# chainable_shift_register.net
KiCad netlist of a schematic drawn in EAGLE
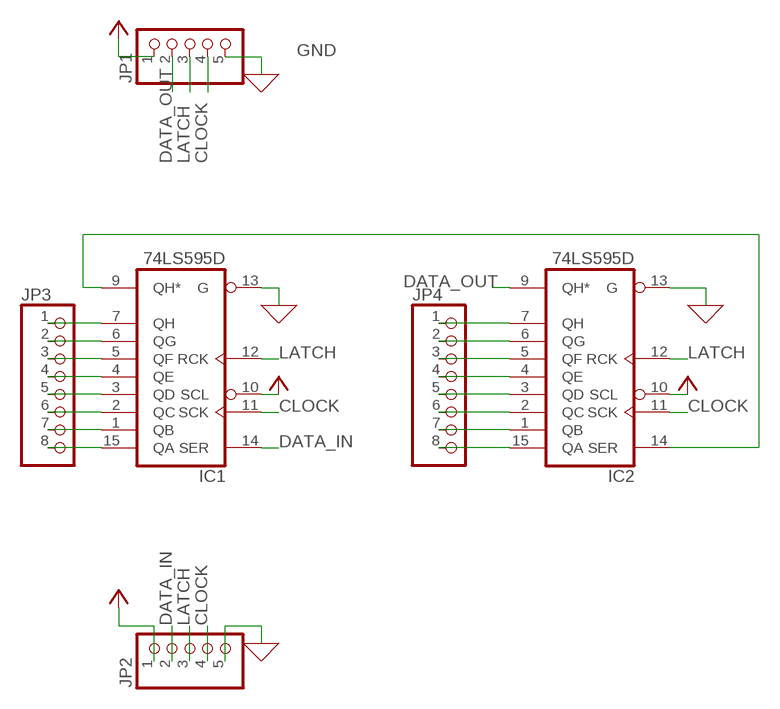
[diagram p0: schematic, sheet 1]

(export (version "E")
  (design (tool "Eeschema 10.0.6"))
  (components
    (comp (ref "IC1")
      (value "74LS595D")
      (footprint "eagle-import:SO16")
      (libsource (lib "eagle-import") (part "74595DLS"))
    )
    (comp (ref "IC2")
      (value "74LS595D")
      (footprint "eagle-import:SO16")
      (libsource (lib "eagle-import") (part "74595DLS"))
    )
    (comp (ref "JP1")
      (value "PINHD-1X5")
      (footprint "eagle-import:1X05")
      (libsource (lib "eagle-import") (part "PINHD-1X5"))
    )
    (comp (ref "JP2")
      (value "PINHD-1X5")
      (footprint "eagle-import:1X05")
      (libsource (lib "eagle-import") (part "PINHD-1X5"))
    )
    (comp (ref "JP3")
      (value "PINHD-1X8")
      (footprint "eagle-import:1X08")
      (libsource (lib "eagle-import") (part "PINHD-1X8"))
    )
    (comp (ref "JP4")
      (value "PINHD-1X8")
      (footprint "eagle-import:1X08")
      (libsource (lib "eagle-import") (part "PINHD-1X8"))
    )
  )
  (nets
    (net (code "1") (name "/CLOCK") (class "Default")
      (node (ref "IC1") (pin "11") (pinfunction "SCK_11") (pintype "input"))
      (node (ref "IC2") (pin "11") (pinfunction "SCK_11") (pintype "input"))
      (node (ref "JP1") (pin "4") (pinfunction "4_4") (pintype "passive"))
      (node (ref "JP2") (pin "4") (pinfunction "4_4") (pintype "passive"))
    )
    (net (code "2") (name "/DATA_IN") (class "Default")
      (node (ref "IC1") (pin "14") (pinfunction "SER_14") (pintype "input"))
      (node (ref "JP2") (pin "2") (pinfunction "2_2") (pintype "passive"))
    )
    (net (code "3") (name "/DATA_OUT") (class "Default")
      (node (ref "IC2") (pin "9") (pinfunction "QH*_9") (pintype "tri_state"))
      (node (ref "JP1") (pin "2") (pinfunction "2_2") (pintype "passive"))
    )
    (net (code "4") (name "/LATCH") (class "Default")
      (node (ref "IC1") (pin "12") (pinfunction "RCK_12") (pintype "input"))
      (node (ref "IC2") (pin "12") (pinfunction "RCK_12") (pintype "input"))
      (node (ref "JP1") (pin "3") (pinfunction "3_3") (pintype "passive"))
      (node (ref "JP2") (pin "3") (pinfunction "3_3") (pintype "passive"))
    )
    (net (code "5") (name "GND") (class "Default")
      (node (ref "IC1") (pin "13") (pinfunction "G_13") (pintype "input"))
      (node (ref "IC2") (pin "13") (pinfunction "G_13") (pintype "input"))
      (node (ref "JP1") (pin "5") (pinfunction "5_5") (pintype "passive"))
      (node (ref "JP2") (pin "5") (pinfunction "5_5") (pintype "passive"))
    )
    (net (code "6") (name "Net-(IC1A-QA)") (class "Default")
      (node (ref "IC1") (pin "15") (pinfunction "QA_15") (pintype "tri_state"))
      (node (ref "JP3") (pin "8") (pinfunction "8_8") (pintype "passive"))
    )
    (net (code "7") (name "Net-(IC1A-QB)") (class "Default")
      (node (ref "IC1") (pin "1") (pinfunction "QB_1") (pintype "tri_state"))
      (node (ref "JP3") (pin "7") (pinfunction "7_7") (pintype "passive"))
    )
    (net (code "8") (name "Net-(IC1A-QC)") (class "Default")
      (node (ref "IC1") (pin "2") (pinfunction "QC_2") (pintype "tri_state"))
      (node (ref "JP3") (pin "6") (pinfunction "6_6") (pintype "passive"))
    )
    (net (code "9") (name "Net-(IC1A-QD)") (class "Default")
      (node (ref "IC1") (pin "3") (pinfunction "QD_3") (pintype "tri_state"))
      (node (ref "JP3") (pin "5") (pinfunction "5_5") (pintype "passive"))
    )
    (net (code "10") (name "Net-(IC1A-QE)") (class "Default")
      (node (ref "IC1") (pin "4") (pinfunction "QE_4") (pintype "tri_state"))
      (node (ref "JP3") (pin "4") (pinfunction "4_4") (pintype "passive"))
    )
    (net (code "11") (name "Net-(IC1A-QF)") (class "Default")
      (node (ref "IC1") (pin "5") (pinfunction "QF_5") (pintype "tri_state"))
      (node (ref "JP3") (pin "3") (pinfunction "3_3") (pintype "passive"))
    )
    (net (code "12") (name "Net-(IC1A-QG)") (class "Default")
      (node (ref "IC1") (pin "6") (pinfunction "QG_6") (pintype "tri_state"))
      (node (ref "JP3") (pin "2") (pinfunction "2_2") (pintype "passive"))
    )
    (net (code "13") (name "Net-(IC1A-QH)") (class "Default")
      (node (ref "IC1") (pin "7") (pinfunction "QH_7") (pintype "tri_state"))
      (node (ref "JP3") (pin "1") (pinfunction "1_1") (pintype "passive"))
    )
    (net (code "14") (name "Net-(IC1A-QH*)") (class "Default")
      (node (ref "IC1") (pin "9") (pinfunction "QH*_9") (pintype "tri_state"))
      (node (ref "IC2") (pin "14") (pinfunction "SER_14") (pintype "input"))
    )
    (net (code "15") (name "Net-(IC2A-QA)") (class "Default")
      (node (ref "IC2") (pin "15") (pinfunction "QA_15") (pintype "tri_state"))
      (node (ref "JP4") (pin "8") (pinfunction "8_8") (pintype "passive"))
    )
    (net (code "16") (name "Net-(IC2A-QB)") (class "Default")
      (node (ref "IC2") (pin "1") (pinfunction "QB_1") (pintype "tri_state"))
      (node (ref "JP4") (pin "7") (pinfunction "7_7") (pintype "passive"))
    )
    (net (code "17") (name "Net-(IC2A-QC)") (class "Default")
      (node (ref "IC2") (pin "2") (pinfunction "QC_2") (pintype "tri_state"))
      (node (ref "JP4") (pin "6") (pinfunction "6_6") (pintype "passive"))
    )
    (net (code "18") (name "Net-(IC2A-QD)") (class "Default")
      (node (ref "IC2") (pin "3") (pinfunction "QD_3") (pintype "tri_state"))
      (node (ref "JP4") (pin "5") (pinfunction "5_5") (pintype "passive"))
    )
    (net (code "19") (name "Net-(IC2A-QE)") (class "Default")
      (node (ref "IC2") (pin "4") (pinfunction "QE_4") (pintype "tri_state"))
      (node (ref "JP4") (pin "4") (pinfunction "4_4") (pintype "passive"))
    )
    (net (code "20") (name "Net-(IC2A-QF)") (class "Default")
      (node (ref "IC2") (pin "5") (pinfunction "QF_5") (pintype "tri_state"))
      (node (ref "JP4") (pin "3") (pinfunction "3_3") (pintype "passive"))
    )
    (net (code "21") (name "Net-(IC2A-QG)") (class "Default")
      (node (ref "IC2") (pin "6") (pinfunction "QG_6") (pintype "tri_state"))
      (node (ref "JP4") (pin "2") (pinfunction "2_2") (pintype "passive"))
    )
    (net (code "22") (name "Net-(IC2A-QH)") (class "Default")
      (node (ref "IC2") (pin "7") (pinfunction "QH_7") (pintype "tri_state"))
      (node (ref "JP4") (pin "1") (pinfunction "1_1") (pintype "passive"))
    )
    (net (code "23") (name "VCC") (class "Default")
      (node (ref "IC1") (pin "10") (pinfunction "SCL_10") (pintype "input"))
      (node (ref "IC2") (pin "10") (pinfunction "SCL_10") (pintype "input"))
      (node (ref "JP1") (pin "1") (pinfunction "1_1") (pintype "passive"))
      (node (ref "JP2") (pin "1") (pinfunction "1_1") (pintype "passive"))
    )
  )
)
